# doppelshift2.net
KiCad netlist of a schematic drawn in EAGLE
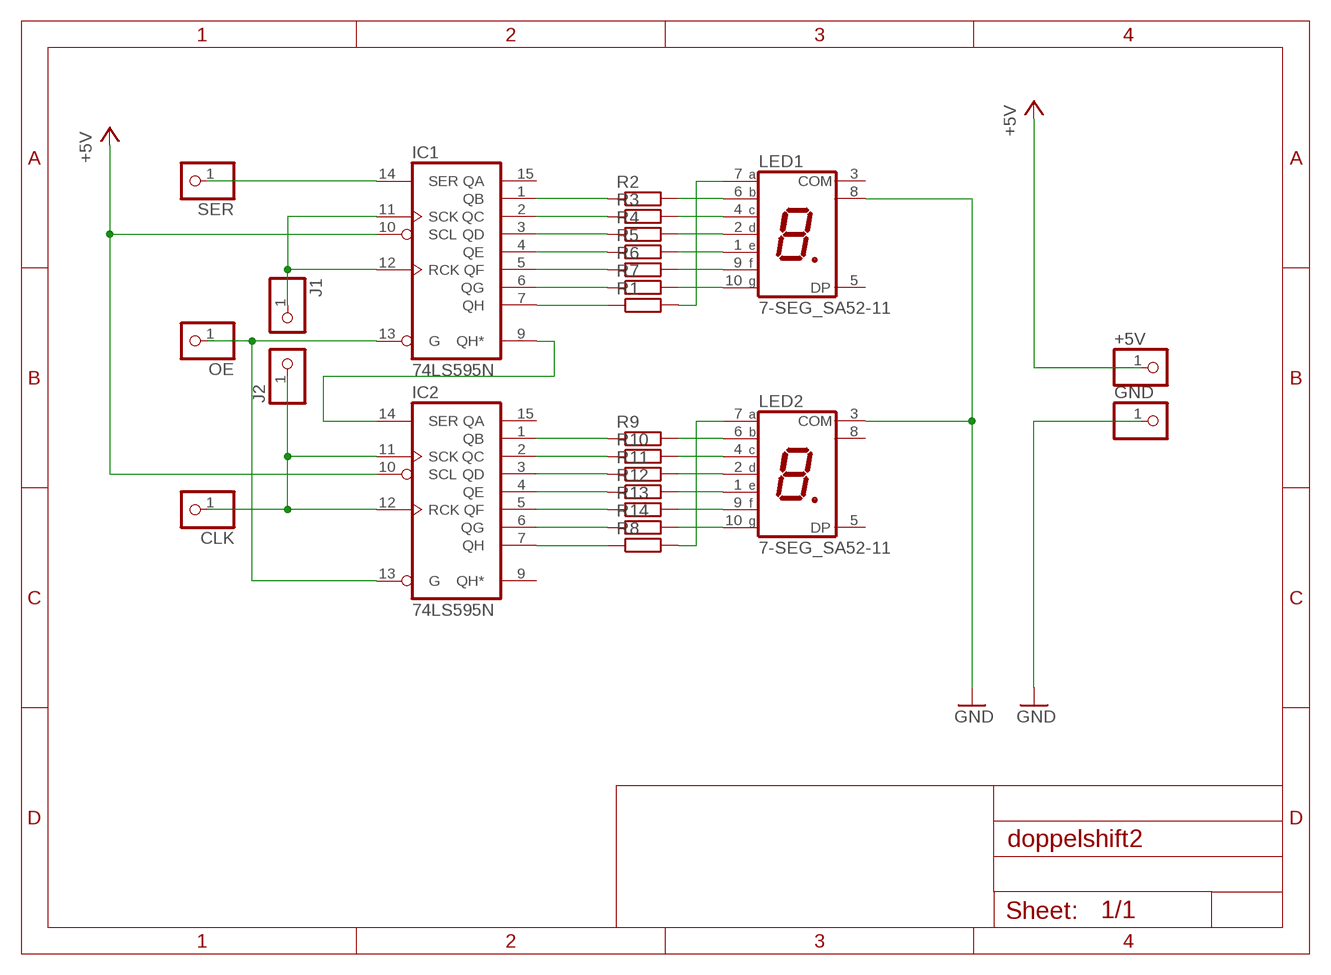
[diagram p0: schematic, sheet 1]

(export (version "E")
  (design (tool "Eeschema 10.0.6"))
  (components
    (comp (ref "+5V")
      (value "PINHD-1X1")
      (footprint "eagle-import:1X01")
      (libsource (lib "eagle-import") (part "PINHD-1X1"))
    )
    (comp (ref "CLK")
      (value "PINHD-1X1")
      (footprint "eagle-import:1X01")
      (libsource (lib "eagle-import") (part "PINHD-1X1"))
    )
    (comp (ref "GND")
      (value "PINHD-1X1")
      (footprint "eagle-import:1X01")
      (libsource (lib "eagle-import") (part "PINHD-1X1"))
    )
    (comp (ref "IC1")
      (value "74LS595N")
      (footprint "eagle-import:DIL16")
      (libsource (lib "eagle-import") (part "74595NLS"))
    )
    (comp (ref "IC2")
      (value "74LS595N")
      (footprint "eagle-import:DIL16")
      (libsource (lib "eagle-import") (part "74595NLS"))
    )
    (comp (ref "J1")
      (value "PINHD-1X1")
      (footprint "eagle-import:1X01")
      (libsource (lib "eagle-import") (part "PINHD-1X1"))
    )
    (comp (ref "J2")
      (value "PINHD-1X1")
      (footprint "eagle-import:1X01")
      (libsource (lib "eagle-import") (part "PINHD-1X1"))
    )
    (comp (ref "LED1")
      (value "7-SEG_SA52-11")
      (footprint "eagle-import:SA52-11")
      (libsource (lib "eagle-import") (part "7-SEG_SA52-11"))
    )
    (comp (ref "LED2")
      (value "7-SEG_SA52-11")
      (footprint "eagle-import:SA52-11")
      (libsource (lib "eagle-import") (part "7-SEG_SA52-11"))
    )
    (comp (ref "OE")
      (value "PINHD-1X1")
      (footprint "eagle-import:1X01")
      (libsource (lib "eagle-import") (part "PINHD-1X1"))
    )
    (comp (ref "R1")
      (value "R-EU_0309/10")
      (footprint "eagle-import:0309_10")
      (libsource (lib "eagle-import") (part "R-EU_0309/10"))
    )
    (comp (ref "R2")
      (value "R-EU_0309/10")
      (footprint "eagle-import:0309_10")
      (libsource (lib "eagle-import") (part "R-EU_0309/10"))
    )
    (comp (ref "R3")
      (value "R-EU_0309/10")
      (footprint "eagle-import:0309_10")
      (libsource (lib "eagle-import") (part "R-EU_0309/10"))
    )
    (comp (ref "R4")
      (value "R-EU_0309/10")
      (footprint "eagle-import:0309_10")
      (libsource (lib "eagle-import") (part "R-EU_0309/10"))
    )
    (comp (ref "R5")
      (value "R-EU_0309/10")
      (footprint "eagle-import:0309_10")
      (libsource (lib "eagle-import") (part "R-EU_0309/10"))
    )
    (comp (ref "R6")
      (value "R-EU_0309/10")
      (footprint "eagle-import:0309_10")
      (libsource (lib "eagle-import") (part "R-EU_0309/10"))
    )
    (comp (ref "R7")
      (value "R-EU_0309/10")
      (footprint "eagle-import:0309_10")
      (libsource (lib "eagle-import") (part "R-EU_0309/10"))
    )
    (comp (ref "R8")
      (value "R-EU_0309/10")
      (footprint "eagle-import:0309_10")
      (libsource (lib "eagle-import") (part "R-EU_0309/10"))
    )
    (comp (ref "R9")
      (value "R-EU_0309/10")
      (footprint "eagle-import:0309_10")
      (libsource (lib "eagle-import") (part "R-EU_0309/10"))
    )
    (comp (ref "R10")
      (value "R-EU_0309/10")
      (footprint "eagle-import:0309_10")
      (libsource (lib "eagle-import") (part "R-EU_0309/10"))
    )
    (comp (ref "R11")
      (value "R-EU_0309/10")
      (footprint "eagle-import:0309_10")
      (libsource (lib "eagle-import") (part "R-EU_0309/10"))
    )
    (comp (ref "R12")
      (value "R-EU_0309/10")
      (footprint "eagle-import:0309_10")
      (libsource (lib "eagle-import") (part "R-EU_0309/10"))
    )
    (comp (ref "R13")
      (value "R-EU_0309/10")
      (footprint "eagle-import:0309_10")
      (libsource (lib "eagle-import") (part "R-EU_0309/10"))
    )
    (comp (ref "R14")
      (value "R-EU_0309/10")
      (footprint "eagle-import:0309_10")
      (libsource (lib "eagle-import") (part "R-EU_0309/10"))
    )
    (comp (ref "SER")
      (value "PINHD-1X1")
      (footprint "eagle-import:1X01")
      (libsource (lib "eagle-import") (part "PINHD-1X1"))
    )
  )
  (nets
    (net (code "1") (name "+5V") (class "Default")
      (node (ref "+5V") (pin "1") (pinfunction "1_1") (pintype "passive"))
      (node (ref "IC1") (pin "10") (pinfunction "SCL_10") (pintype "input"))
      (node (ref "IC2") (pin "10") (pinfunction "SCL_10") (pintype "input"))
    )
    (net (code "2") (name "GND") (class "Default")
      (node (ref "GND") (pin "1") (pinfunction "1_1") (pintype "passive"))
      (node (ref "LED1") (pin "8") (pinfunction "COM_8") (pintype "passive"))
      (node (ref "LED2") (pin "3") (pinfunction "COM_3") (pintype "passive"))
    )
    (net (code "3") (name "Net-(IC1A-G)") (class "Default")
      (node (ref "IC1") (pin "13") (pinfunction "G_13") (pintype "input"))
      (node (ref "IC2") (pin "13") (pinfunction "G_13") (pintype "input"))
      (node (ref "OE") (pin "1") (pinfunction "1_1") (pintype "passive"))
    )
    (net (code "4") (name "Net-(IC1A-QB)") (class "Default")
      (node (ref "IC1") (pin "1") (pinfunction "QB_1") (pintype "tri_state"))
      (node (ref "R2") (pin "1") (pinfunction "1_1") (pintype "passive"))
    )
    (net (code "5") (name "Net-(IC1A-QC)") (class "Default")
      (node (ref "IC1") (pin "2") (pinfunction "QC_2") (pintype "tri_state"))
      (node (ref "R3") (pin "1") (pinfunction "1_1") (pintype "passive"))
    )
    (net (code "6") (name "Net-(IC1A-QD)") (class "Default")
      (node (ref "IC1") (pin "3") (pinfunction "QD_3") (pintype "tri_state"))
      (node (ref "R4") (pin "1") (pinfunction "1_1") (pintype "passive"))
    )
    (net (code "7") (name "Net-(IC1A-QE)") (class "Default")
      (node (ref "IC1") (pin "4") (pinfunction "QE_4") (pintype "tri_state"))
      (node (ref "R5") (pin "1") (pinfunction "1_1") (pintype "passive"))
    )
    (net (code "8") (name "Net-(IC1A-QF)") (class "Default")
      (node (ref "IC1") (pin "5") (pinfunction "QF_5") (pintype "tri_state"))
      (node (ref "R6") (pin "1") (pinfunction "1_1") (pintype "passive"))
    )
    (net (code "9") (name "Net-(IC1A-QG)") (class "Default")
      (node (ref "IC1") (pin "6") (pinfunction "QG_6") (pintype "tri_state"))
      (node (ref "R7") (pin "1") (pinfunction "1_1") (pintype "passive"))
    )
    (net (code "10") (name "Net-(IC1A-QH)") (class "Default")
      (node (ref "IC1") (pin "7") (pinfunction "QH_7") (pintype "tri_state"))
      (node (ref "R1") (pin "1") (pinfunction "1_1") (pintype "passive"))
    )
    (net (code "11") (name "Net-(IC1A-QH*)") (class "Default")
      (node (ref "IC1") (pin "9") (pinfunction "QH*_9") (pintype "tri_state"))
      (node (ref "IC2") (pin "14") (pinfunction "SER_14") (pintype "input"))
    )
    (net (code "12") (name "Net-(IC1A-RCK)") (class "Default")
      (node (ref "IC1") (pin "11") (pinfunction "SCK_11") (pintype "input"))
      (node (ref "IC1") (pin "12") (pinfunction "RCK_12") (pintype "input"))
      (node (ref "J1") (pin "1") (pinfunction "1_1") (pintype "passive"))
    )
    (net (code "13") (name "Net-(IC1A-SER)") (class "Default")
      (node (ref "IC1") (pin "14") (pinfunction "SER_14") (pintype "input"))
      (node (ref "SER") (pin "1") (pinfunction "1_1") (pintype "passive"))
    )
    (net (code "14") (name "Net-(IC2A-QB)") (class "Default")
      (node (ref "IC2") (pin "1") (pinfunction "QB_1") (pintype "tri_state"))
      (node (ref "R9") (pin "1") (pinfunction "1_1") (pintype "passive"))
    )
    (net (code "15") (name "Net-(IC2A-QC)") (class "Default")
      (node (ref "IC2") (pin "2") (pinfunction "QC_2") (pintype "tri_state"))
      (node (ref "R10") (pin "1") (pinfunction "1_1") (pintype "passive"))
    )
    (net (code "16") (name "Net-(IC2A-QD)") (class "Default")
      (node (ref "IC2") (pin "3") (pinfunction "QD_3") (pintype "tri_state"))
      (node (ref "R11") (pin "1") (pinfunction "1_1") (pintype "passive"))
    )
    (net (code "17") (name "Net-(IC2A-QE)") (class "Default")
      (node (ref "IC2") (pin "4") (pinfunction "QE_4") (pintype "tri_state"))
      (node (ref "R12") (pin "1") (pinfunction "1_1") (pintype "passive"))
    )
    (net (code "18") (name "Net-(IC2A-QF)") (class "Default")
      (node (ref "IC2") (pin "5") (pinfunction "QF_5") (pintype "tri_state"))
      (node (ref "R13") (pin "1") (pinfunction "1_1") (pintype "passive"))
    )
    (net (code "19") (name "Net-(IC2A-QG)") (class "Default")
      (node (ref "IC2") (pin "6") (pinfunction "QG_6") (pintype "tri_state"))
      (node (ref "R14") (pin "1") (pinfunction "1_1") (pintype "passive"))
    )
    (net (code "20") (name "Net-(IC2A-QH)") (class "Default")
      (node (ref "IC2") (pin "7") (pinfunction "QH_7") (pintype "tri_state"))
      (node (ref "R8") (pin "1") (pinfunction "1_1") (pintype "passive"))
    )
    (net (code "21") (name "Net-(IC2A-RCK)") (class "Default")
      (node (ref "CLK") (pin "1") (pinfunction "1_1") (pintype "passive"))
      (node (ref "IC2") (pin "11") (pinfunction "SCK_11") (pintype "input"))
      (node (ref "IC2") (pin "12") (pinfunction "RCK_12") (pintype "input"))
      (node (ref "J2") (pin "1") (pinfunction "1_1") (pintype "passive"))
    )
    (net (code "22") (name "Net-(LED1-A)") (class "Default")
      (node (ref "LED1") (pin "7") (pinfunction "A_7") (pintype "passive"))
      (node (ref "R1") (pin "2") (pinfunction "2_2") (pintype "passive"))
    )
    (net (code "23") (name "Net-(LED1-B)") (class "Default")
      (node (ref "LED1") (pin "6") (pinfunction "B_6") (pintype "passive"))
      (node (ref "R2") (pin "2") (pinfunction "2_2") (pintype "passive"))
    )
    (net (code "24") (name "Net-(LED1-C)") (class "Default")
      (node (ref "LED1") (pin "4") (pinfunction "C_4") (pintype "passive"))
      (node (ref "R3") (pin "2") (pinfunction "2_2") (pintype "passive"))
    )
    (net (code "25") (name "Net-(LED1-D)") (class "Default")
      (node (ref "LED1") (pin "2") (pinfunction "D_2") (pintype "passive"))
      (node (ref "R4") (pin "2") (pinfunction "2_2") (pintype "passive"))
    )
    (net (code "26") (name "Net-(LED1-E)") (class "Default")
      (node (ref "LED1") (pin "1") (pinfunction "E_1") (pintype "passive"))
      (node (ref "R5") (pin "2") (pinfunction "2_2") (pintype "passive"))
    )
    (net (code "27") (name "Net-(LED1-F)") (class "Default")
      (node (ref "LED1") (pin "9") (pinfunction "F_9") (pintype "passive"))
      (node (ref "R6") (pin "2") (pinfunction "2_2") (pintype "passive"))
    )
    (net (code "28") (name "Net-(LED1-G)") (class "Default")
      (node (ref "LED1") (pin "10") (pinfunction "G_10") (pintype "passive"))
      (node (ref "R7") (pin "2") (pinfunction "2_2") (pintype "passive"))
    )
    (net (code "29") (name "Net-(LED2-A)") (class "Default")
      (node (ref "LED2") (pin "7") (pinfunction "A_7") (pintype "passive"))
      (node (ref "R8") (pin "2") (pinfunction "2_2") (pintype "passive"))
    )
    (net (code "30") (name "Net-(LED2-B)") (class "Default")
      (node (ref "LED2") (pin "6") (pinfunction "B_6") (pintype "passive"))
      (node (ref "R9") (pin "2") (pinfunction "2_2") (pintype "passive"))
    )
    (net (code "31") (name "Net-(LED2-C)") (class "Default")
      (node (ref "LED2") (pin "4") (pinfunction "C_4") (pintype "passive"))
      (node (ref "R10") (pin "2") (pinfunction "2_2") (pintype "passive"))
    )
    (net (code "32") (name "Net-(LED2-D)") (class "Default")
      (node (ref "LED2") (pin "2") (pinfunction "D_2") (pintype "passive"))
      (node (ref "R11") (pin "2") (pinfunction "2_2") (pintype "passive"))
    )
    (net (code "33") (name "Net-(LED2-E)") (class "Default")
      (node (ref "LED2") (pin "1") (pinfunction "E_1") (pintype "passive"))
      (node (ref "R12") (pin "2") (pinfunction "2_2") (pintype "passive"))
    )
    (net (code "34") (name "Net-(LED2-F)") (class "Default")
      (node (ref "LED2") (pin "9") (pinfunction "F_9") (pintype "passive"))
      (node (ref "R13") (pin "2") (pinfunction "2_2") (pintype "passive"))
    )
    (net (code "35") (name "Net-(LED2-G)") (class "Default")
      (node (ref "LED2") (pin "10") (pinfunction "G_10") (pintype "passive"))
      (node (ref "R14") (pin "2") (pinfunction "2_2") (pintype "passive"))
    )
    (net (code "36") (name "unconnected-(IC1A-QA-Pad15)") (class "Default")
      (node (ref "IC1") (pin "15") (pinfunction "QA_15") (pintype "tri_state"))
    )
    (net (code "37") (name "unconnected-(IC2A-QA-Pad15)") (class "Default")
      (node (ref "IC2") (pin "15") (pinfunction "QA_15") (pintype "tri_state"))
    )
    (net (code "38") (name "unconnected-(IC2A-QH*-Pad9)") (class "Default")
      (node (ref "IC2") (pin "9") (pinfunction "QH*_9") (pintype "tri_state"))
    )
    (net (code "39") (name "unconnected-(LED1-COM-Pad3)") (class "Default")
      (node (ref "LED1") (pin "3") (pinfunction "COM_3") (pintype "passive"))
    )
    (net (code "40") (name "unconnected-(LED1-DP-Pad5)") (class "Default")
      (node (ref "LED1") (pin "5") (pinfunction "DP_5") (pintype "passive"))
    )
    (net (code "41") (name "unconnected-(LED2-COM-Pad8)") (class "Default")
      (node (ref "LED2") (pin "8") (pinfunction "COM_8") (pintype "passive"))
    )
    (net (code "42") (name "unconnected-(LED2-DP-Pad5)") (class "Default")
      (node (ref "LED2") (pin "5") (pinfunction "DP_5") (pintype "passive"))
    )
  )
)
